# rpi.net
KiCad netlist of a schematic drawn in Altium Designer
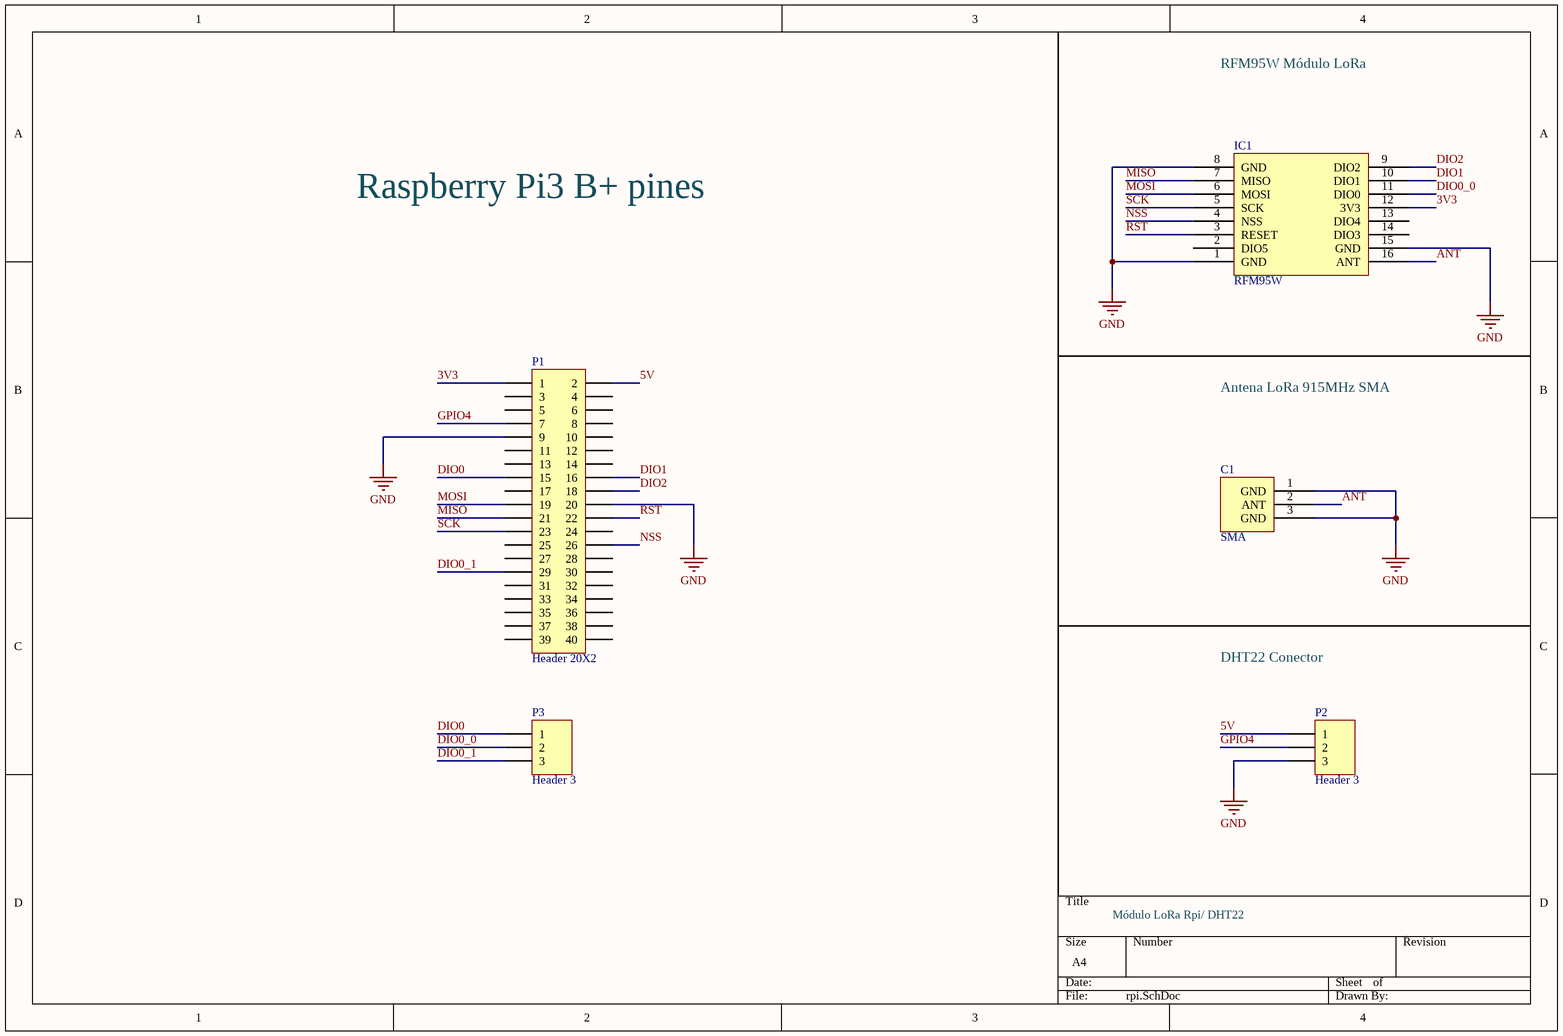
[diagram p0: rpi.SchDoc]

(export (version "E")
  (design (tool "Eeschema 10.0.6"))
  (components
    (comp (ref "C1") (value "SMA") (footprint "SMA") (libsource (lib "ComponentesTesis") (part "SMA")))
    (comp (ref "IC1")
      (value "RFM95W")
      (footprint "RFM95W")
      (libsource (lib "ComponentesTesis") (part "RFM95W"))
    )
    (comp (ref "P1")
      (value "Header 20X2")
      (footprint "HDR2X20")
      (description "Header, 20-Pin, Dual row")
      (fields (field (name "PUBLISHER") "Altium Limited"))
      (libsource (lib "Miscellaneous Connectors") (part "Header 20X2"))
    )
    (comp (ref "P2")
      (value "Header 3")
      (footprint "HDR1X3")
      (description "Header, 3-Pin")
      (fields (field (name "PUBLISHER") "Altium Limited"))
      (libsource (lib "Miscellaneous Connectors") (part "Header 3"))
    )
    (comp (ref "P3")
      (value "Header 3")
      (footprint "HDR1X3")
      (description "Header, 3-Pin")
      (fields (field (name "PUBLISHER") "Altium Limited"))
      (libsource (lib "Miscellaneous Connectors") (part "Header 3"))
    )
  )
  (nets
    (net (code "1") (name "/3V3") (class "Default")
      (node (ref "IC1") (pin "12") (pinfunction "3V3_12") (pintype "power_in"))
      (node (ref "P1") (pin "1") (pinfunction "1_1") (pintype "passive"))
    )
    (net (code "2") (name "/5V") (class "Default")
      (node (ref "P1") (pin "2") (pinfunction "2_2") (pintype "passive"))
      (node (ref "P2") (pin "1") (pinfunction "1_1") (pintype "passive"))
    )
    (net (code "3") (name "/ANT") (class "Default")
      (node (ref "C1") (pin "2") (pinfunction "ANT_2") (pintype "passive"))
      (node (ref "IC1") (pin "16") (pinfunction "ANT_16") (pintype "passive"))
    )
    (net (code "4") (name "/DIO0") (class "Default")
      (node (ref "P1") (pin "15") (pinfunction "15_15") (pintype "passive"))
      (node (ref "P3") (pin "1") (pinfunction "1_1") (pintype "passive"))
    )
    (net (code "5") (name "/DIO0_0") (class "Default")
      (node (ref "IC1") (pin "11") (pinfunction "DIO0_11") (pintype "passive"))
      (node (ref "P3") (pin "2") (pinfunction "2_2") (pintype "passive"))
    )
    (net (code "6") (name "/DIO0_1") (class "Default")
      (node (ref "P1") (pin "29") (pinfunction "29_29") (pintype "passive"))
      (node (ref "P3") (pin "3") (pinfunction "3_3") (pintype "passive"))
    )
    (net (code "7") (name "/DIO1") (class "Default")
      (node (ref "IC1") (pin "10") (pinfunction "DIO1_10") (pintype "passive"))
      (node (ref "P1") (pin "16") (pinfunction "16_16") (pintype "passive"))
    )
    (net (code "8") (name "/DIO2") (class "Default")
      (node (ref "IC1") (pin "9") (pinfunction "DIO2_9") (pintype "passive"))
      (node (ref "P1") (pin "18") (pinfunction "18_18") (pintype "passive"))
    )
    (net (code "9") (name "/GPIO4") (class "Default")
      (node (ref "P1") (pin "7") (pinfunction "7_7") (pintype "passive"))
      (node (ref "P2") (pin "2") (pinfunction "2_2") (pintype "passive"))
    )
    (net (code "10") (name "/MISO") (class "Default")
      (node (ref "IC1") (pin "7") (pinfunction "MISO_7") (pintype "passive"))
      (node (ref "P1") (pin "21") (pinfunction "21_21") (pintype "passive"))
    )
    (net (code "11") (name "/MOSI") (class "Default")
      (node (ref "IC1") (pin "6") (pinfunction "MOSI_6") (pintype "passive"))
      (node (ref "P1") (pin "19") (pinfunction "19_19") (pintype "passive"))
    )
    (net (code "12") (name "/NSS") (class "Default")
      (node (ref "IC1") (pin "4") (pinfunction "NSS_4") (pintype "passive"))
      (node (ref "P1") (pin "26") (pinfunction "26_26") (pintype "passive"))
    )
    (net (code "13") (name "/RST") (class "Default")
      (node (ref "IC1") (pin "3") (pinfunction "RESET_3") (pintype "passive"))
      (node (ref "P1") (pin "22") (pinfunction "22_22") (pintype "passive"))
    )
    (net (code "14") (name "/SCK") (class "Default")
      (node (ref "IC1") (pin "5") (pinfunction "SCK_5") (pintype "passive"))
      (node (ref "P1") (pin "23") (pinfunction "23_23") (pintype "passive"))
    )
    (net (code "15") (name "GND") (class "Default")
      (node (ref "C1") (pin "1") (pinfunction "GND_1") (pintype "passive"))
      (node (ref "C1") (pin "3") (pinfunction "GND_3") (pintype "passive"))
      (node (ref "IC1") (pin "1") (pinfunction "GND_1") (pintype "power_in"))
      (node (ref "IC1") (pin "15") (pinfunction "GND_15") (pintype "power_in"))
      (node (ref "IC1") (pin "8") (pinfunction "GND_8") (pintype "power_in"))
      (node (ref "P1") (pin "20") (pinfunction "20_20") (pintype "passive"))
      (node (ref "P1") (pin "9") (pinfunction "9_9") (pintype "passive"))
      (node (ref "P2") (pin "3") (pinfunction "3_3") (pintype "passive"))
    )
    (net (code "16") (name "unconnected-(IC1-DIO3-Pad14)") (class "Default")
      (node (ref "IC1") (pin "14") (pinfunction "DIO3_14") (pintype "passive"))
    )
    (net (code "17") (name "unconnected-(IC1-DIO4-Pad13)") (class "Default")
      (node (ref "IC1") (pin "13") (pinfunction "DIO4_13") (pintype "passive"))
    )
    (net (code "18") (name "unconnected-(IC1-DIO5-Pad2)") (class "Default")
      (node (ref "IC1") (pin "2") (pinfunction "DIO5_2") (pintype "passive"))
    )
    (net (code "19") (name "unconnected-(P1-Pad3)") (class "Default")
      (node (ref "P1") (pin "3") (pinfunction "3_3") (pintype "passive"))
    )
    (net (code "20") (name "unconnected-(P1-Pad4)") (class "Default")
      (node (ref "P1") (pin "4") (pinfunction "4_4") (pintype "passive"))
    )
    (net (code "21") (name "unconnected-(P1-Pad5)") (class "Default")
      (node (ref "P1") (pin "5") (pinfunction "5_5") (pintype "passive"))
    )
    (net (code "22") (name "unconnected-(P1-Pad6)") (class "Default")
      (node (ref "P1") (pin "6") (pinfunction "6_6") (pintype "passive"))
    )
    (net (code "23") (name "unconnected-(P1-Pad8)") (class "Default")
      (node (ref "P1") (pin "8") (pinfunction "8_8") (pintype "passive"))
    )
    (net (code "24") (name "unconnected-(P1-Pad10)") (class "Default")
      (node (ref "P1") (pin "10") (pinfunction "10_10") (pintype "passive"))
    )
    (net (code "25") (name "unconnected-(P1-Pad11)") (class "Default")
      (node (ref "P1") (pin "11") (pinfunction "11_11") (pintype "passive"))
    )
    (net (code "26") (name "unconnected-(P1-Pad12)") (class "Default")
      (node (ref "P1") (pin "12") (pinfunction "12_12") (pintype "passive"))
    )
    (net (code "27") (name "unconnected-(P1-Pad13)") (class "Default")
      (node (ref "P1") (pin "13") (pinfunction "13_13") (pintype "passive"))
    )
    (net (code "28") (name "unconnected-(P1-Pad14)") (class "Default")
      (node (ref "P1") (pin "14") (pinfunction "14_14") (pintype "passive"))
    )
    (net (code "29") (name "unconnected-(P1-Pad17)") (class "Default")
      (node (ref "P1") (pin "17") (pinfunction "17_17") (pintype "passive"))
    )
    (net (code "30") (name "unconnected-(P1-Pad24)") (class "Default")
      (node (ref "P1") (pin "24") (pinfunction "24_24") (pintype "passive"))
    )
    (net (code "31") (name "unconnected-(P1-Pad25)") (class "Default")
      (node (ref "P1") (pin "25") (pinfunction "25_25") (pintype "passive"))
    )
    (net (code "32") (name "unconnected-(P1-Pad27)") (class "Default")
      (node (ref "P1") (pin "27") (pinfunction "27_27") (pintype "passive"))
    )
    (net (code "33") (name "unconnected-(P1-Pad28)") (class "Default")
      (node (ref "P1") (pin "28") (pinfunction "28_28") (pintype "passive"))
    )
    (net (code "34") (name "unconnected-(P1-Pad30)") (class "Default")
      (node (ref "P1") (pin "30") (pinfunction "30_30") (pintype "passive"))
    )
    (net (code "35") (name "unconnected-(P1-Pad31)") (class "Default")
      (node (ref "P1") (pin "31") (pinfunction "31_31") (pintype "passive"))
    )
    (net (code "36") (name "unconnected-(P1-Pad32)") (class "Default")
      (node (ref "P1") (pin "32") (pinfunction "32_32") (pintype "passive"))
    )
    (net (code "37") (name "unconnected-(P1-Pad33)") (class "Default")
      (node (ref "P1") (pin "33") (pinfunction "33_33") (pintype "passive"))
    )
    (net (code "38") (name "unconnected-(P1-Pad34)") (class "Default")
      (node (ref "P1") (pin "34") (pinfunction "34_34") (pintype "passive"))
    )
    (net (code "39") (name "unconnected-(P1-Pad35)") (class "Default")
      (node (ref "P1") (pin "35") (pinfunction "35_35") (pintype "passive"))
    )
    (net (code "40") (name "unconnected-(P1-Pad36)") (class "Default")
      (node (ref "P1") (pin "36") (pinfunction "36_36") (pintype "passive"))
    )
    (net (code "41") (name "unconnected-(P1-Pad37)") (class "Default")
      (node (ref "P1") (pin "37") (pinfunction "37_37") (pintype "passive"))
    )
    (net (code "42") (name "unconnected-(P1-Pad38)") (class "Default")
      (node (ref "P1") (pin "38") (pinfunction "38_38") (pintype "passive"))
    )
    (net (code "43") (name "unconnected-(P1-Pad39)") (class "Default")
      (node (ref "P1") (pin "39") (pinfunction "39_39") (pintype "passive"))
    )
    (net (code "44") (name "unconnected-(P1-Pad40)") (class "Default")
      (node (ref "P1") (pin "40") (pinfunction "40_40") (pintype "passive"))
    )
  )
)
